# 04_-_BUTTON.net
KiCad netlist of a schematic drawn in Altium Designer
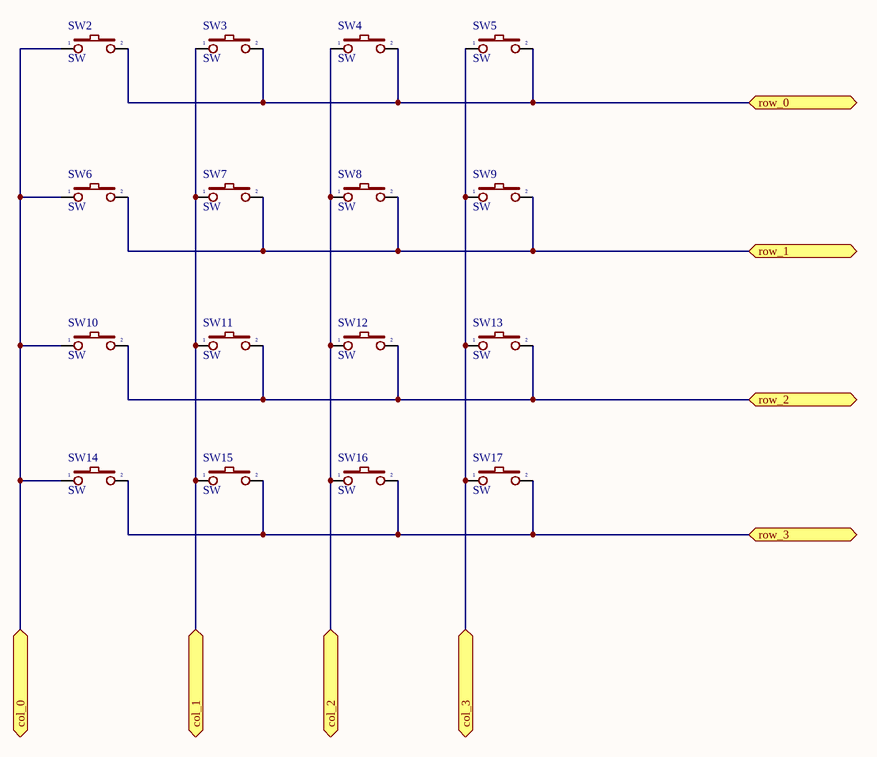
[diagram p0: 04 - BUTTON.SchDoc]

(export (version "E")
  (design (tool "Eeschema 10.0.6"))
  (components
    (comp (ref "SW2")
      (value "SW")
      (footprint "SW2")
      (description "Switch button 2 pin")
      (libsource (lib "My Library.~(5)") (part "SW2"))
    )
    (comp (ref "SW3")
      (value "SW")
      (footprint "SW2")
      (description "Switch button 2 pin")
      (libsource (lib "My Library.~(5)") (part "SW2"))
    )
    (comp (ref "SW4")
      (value "SW")
      (footprint "SW2")
      (description "Switch button 2 pin")
      (libsource (lib "My Library.~(5)") (part "SW2"))
    )
    (comp (ref "SW5")
      (value "SW")
      (footprint "SW2")
      (description "Switch button 2 pin")
      (libsource (lib "My Library.~(5)") (part "SW2"))
    )
    (comp (ref "SW6")
      (value "SW")
      (footprint "SW2")
      (description "Switch button 2 pin")
      (libsource (lib "My Library.~(5)") (part "SW2"))
    )
    (comp (ref "SW7")
      (value "SW")
      (footprint "SW2")
      (description "Switch button 2 pin")
      (libsource (lib "My Library.~(5)") (part "SW2"))
    )
    (comp (ref "SW8")
      (value "SW")
      (footprint "SW2")
      (description "Switch button 2 pin")
      (libsource (lib "My Library.~(5)") (part "SW2"))
    )
    (comp (ref "SW9")
      (value "SW")
      (footprint "SW2")
      (description "Switch button 2 pin")
      (libsource (lib "My Library.~(5)") (part "SW2"))
    )
    (comp (ref "SW10")
      (value "SW")
      (footprint "SW2")
      (description "Switch button 2 pin")
      (libsource (lib "My Library.~(5)") (part "SW2"))
    )
    (comp (ref "SW11")
      (value "SW")
      (footprint "SW2")
      (description "Switch button 2 pin")
      (libsource (lib "My Library.~(5)") (part "SW2"))
    )
    (comp (ref "SW12")
      (value "SW")
      (footprint "SW2")
      (description "Switch button 2 pin")
      (libsource (lib "My Library.~(5)") (part "SW2"))
    )
    (comp (ref "SW13")
      (value "SW")
      (footprint "SW2")
      (description "Switch button 2 pin")
      (libsource (lib "My Library.~(5)") (part "SW2"))
    )
    (comp (ref "SW14")
      (value "SW")
      (footprint "SW2")
      (description "Switch button 2 pin")
      (libsource (lib "My Library.~(5)") (part "SW2"))
    )
    (comp (ref "SW15")
      (value "SW")
      (footprint "SW2")
      (description "Switch button 2 pin")
      (libsource (lib "My Library.~(5)") (part "SW2"))
    )
    (comp (ref "SW16")
      (value "SW")
      (footprint "SW2")
      (description "Switch button 2 pin")
      (libsource (lib "My Library.~(5)") (part "SW2"))
    )
    (comp (ref "SW17")
      (value "SW")
      (footprint "SW2")
      (description "Switch button 2 pin")
      (libsource (lib "My Library.~(5)") (part "SW2"))
    )
  )
  (nets
    (net (code "1") (name "/col_0") (class "Default")
      (node (ref "SW10") (pin "1") (pinfunction "1_1") (pintype "passive"))
      (node (ref "SW14") (pin "1") (pinfunction "1_1") (pintype "passive"))
      (node (ref "SW2") (pin "1") (pinfunction "1_1") (pintype "passive"))
      (node (ref "SW6") (pin "1") (pinfunction "1_1") (pintype "passive"))
    )
    (net (code "2") (name "/col_1") (class "Default")
      (node (ref "SW11") (pin "1") (pinfunction "1_1") (pintype "passive"))
      (node (ref "SW15") (pin "1") (pinfunction "1_1") (pintype "passive"))
      (node (ref "SW3") (pin "1") (pinfunction "1_1") (pintype "passive"))
      (node (ref "SW7") (pin "1") (pinfunction "1_1") (pintype "passive"))
    )
    (net (code "3") (name "/col_2") (class "Default")
      (node (ref "SW12") (pin "1") (pinfunction "1_1") (pintype "passive"))
      (node (ref "SW16") (pin "1") (pinfunction "1_1") (pintype "passive"))
      (node (ref "SW4") (pin "1") (pinfunction "1_1") (pintype "passive"))
      (node (ref "SW8") (pin "1") (pinfunction "1_1") (pintype "passive"))
    )
    (net (code "4") (name "/col_3") (class "Default")
      (node (ref "SW13") (pin "1") (pinfunction "1_1") (pintype "passive"))
      (node (ref "SW17") (pin "1") (pinfunction "1_1") (pintype "passive"))
      (node (ref "SW5") (pin "1") (pinfunction "1_1") (pintype "passive"))
      (node (ref "SW9") (pin "1") (pinfunction "1_1") (pintype "passive"))
    )
    (net (code "5") (name "/row_0") (class "Default")
      (node (ref "SW2") (pin "2") (pinfunction "2_2") (pintype "passive"))
      (node (ref "SW3") (pin "2") (pinfunction "2_2") (pintype "passive"))
      (node (ref "SW4") (pin "2") (pinfunction "2_2") (pintype "passive"))
      (node (ref "SW5") (pin "2") (pinfunction "2_2") (pintype "passive"))
    )
    (net (code "6") (name "/row_1") (class "Default")
      (node (ref "SW6") (pin "2") (pinfunction "2_2") (pintype "passive"))
      (node (ref "SW7") (pin "2") (pinfunction "2_2") (pintype "passive"))
      (node (ref "SW8") (pin "2") (pinfunction "2_2") (pintype "passive"))
      (node (ref "SW9") (pin "2") (pinfunction "2_2") (pintype "passive"))
    )
    (net (code "7") (name "/row_2") (class "Default")
      (node (ref "SW10") (pin "2") (pinfunction "2_2") (pintype "passive"))
      (node (ref "SW11") (pin "2") (pinfunction "2_2") (pintype "passive"))
      (node (ref "SW12") (pin "2") (pinfunction "2_2") (pintype "passive"))
      (node (ref "SW13") (pin "2") (pinfunction "2_2") (pintype "passive"))
    )
    (net (code "8") (name "/row_3") (class "Default")
      (node (ref "SW14") (pin "2") (pinfunction "2_2") (pintype "passive"))
      (node (ref "SW15") (pin "2") (pinfunction "2_2") (pintype "passive"))
      (node (ref "SW16") (pin "2") (pinfunction "2_2") (pintype "passive"))
      (node (ref "SW17") (pin "2") (pinfunction "2_2") (pintype "passive"))
    )
  )
)
